# Esquema_PowerBox1.net
KiCad netlist of a schematic drawn in EAGLE
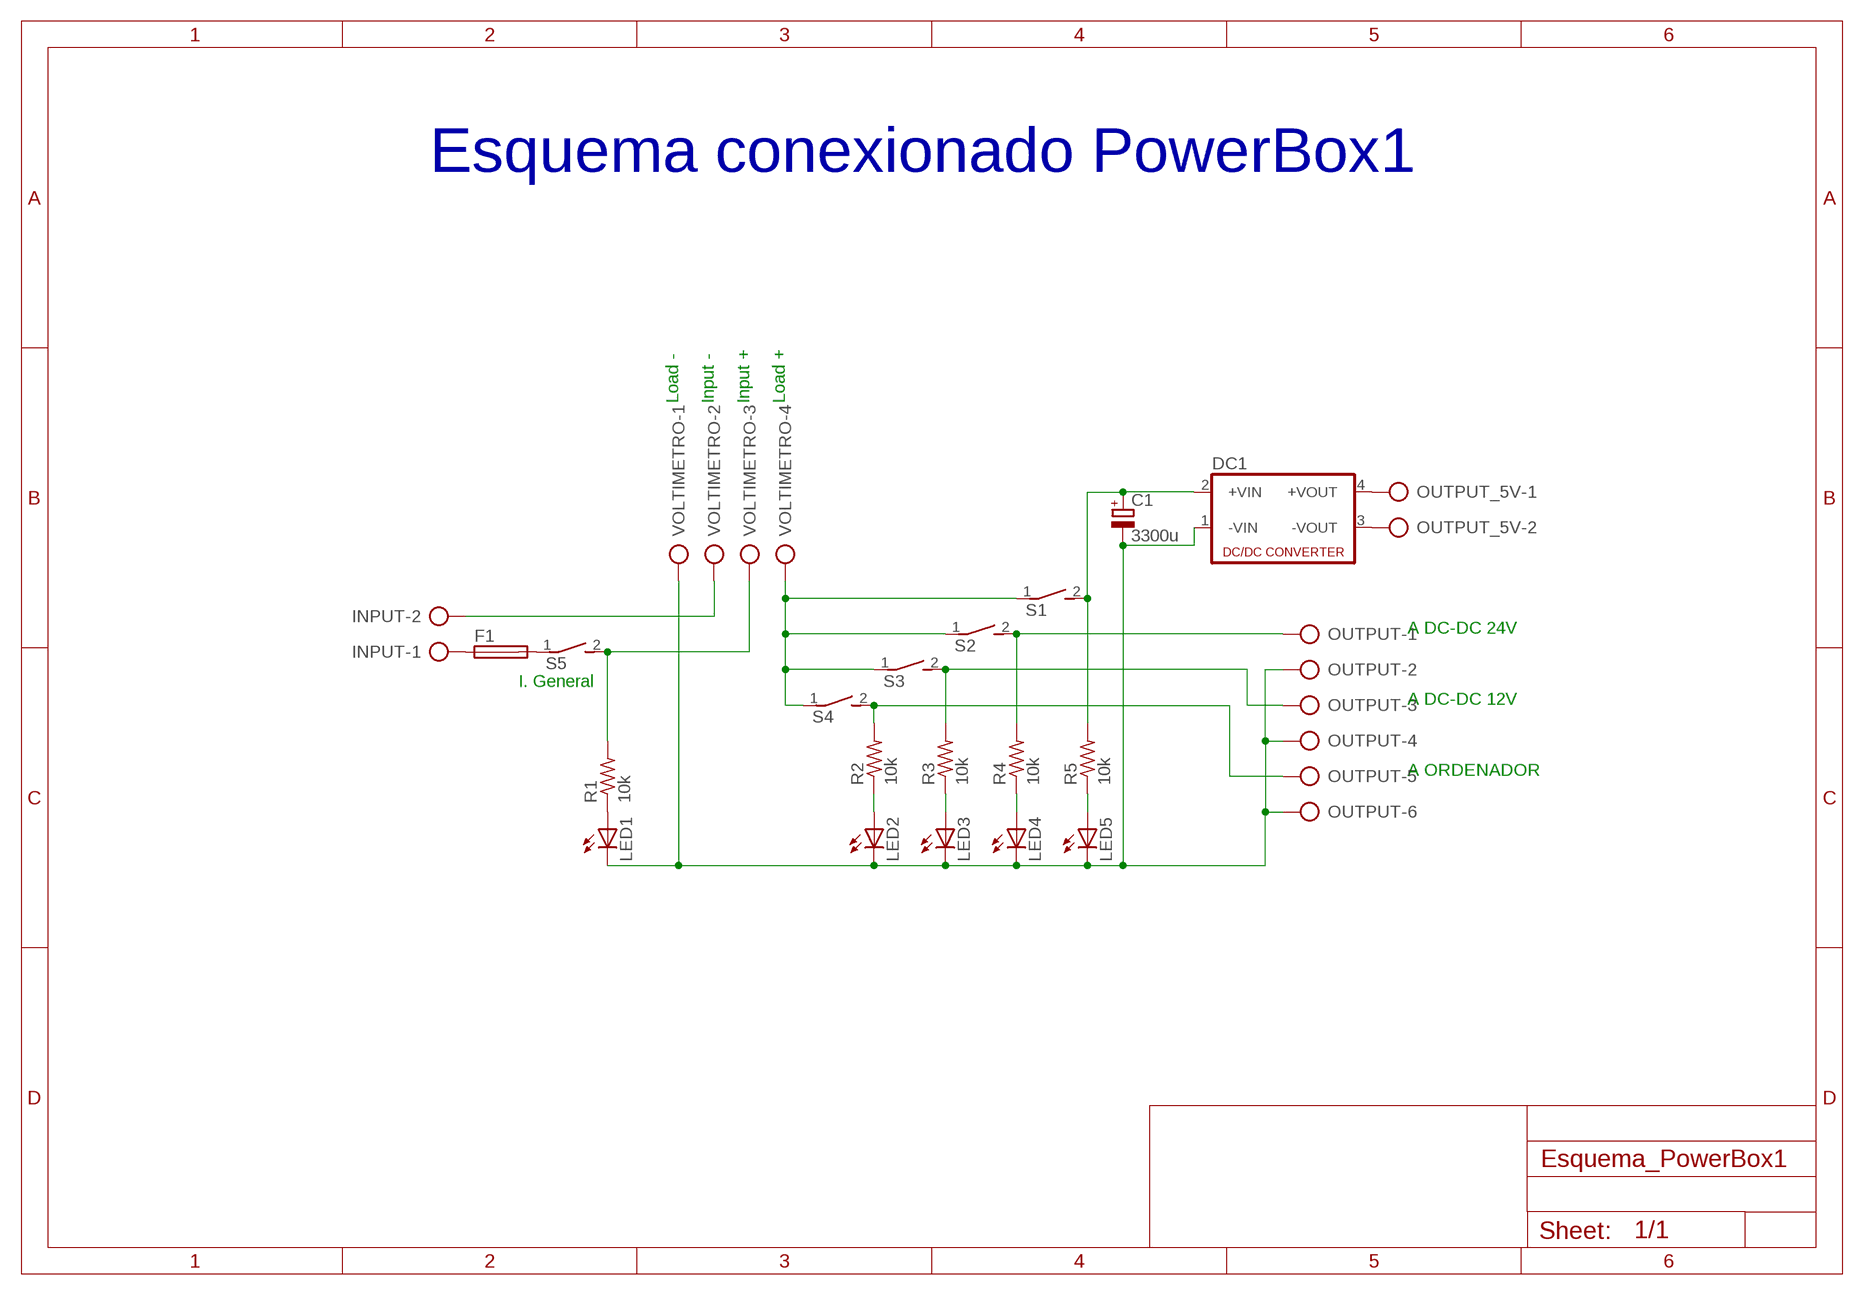
[diagram p0: schematic, sheet 1]

(export (version "E")
  (design (tool "Eeschema 10.0.6"))
  (components
    (comp (ref "C1")
      (value "3300u")
      (footprint "eagle-import:150CLZ-1014")
      (libsource (lib "eagle-import") (part "CPOL-EU150CLZ-1014"))
    )
    (comp (ref "DC1")
      (value "NME")
      (footprint "eagle-import:NME")
      (fields (field (name "MF") "C & D TECHNOLOGIES, INC") (field (name "MPN") "NME1205D"))
      (libsource (lib "eagle-import") (part "NME"))
    )
    (comp (ref "F1")
      (value "PICOFUSE")
      (footprint "eagle-import:PICOFUSE")
      (libsource (lib "eagle-import") (part "PICOFUSE"))
    )
    (comp (ref "INPUT")
      (value "AK500/2")
      (footprint "eagle-import:AK500_2")
      (libsource (lib "eagle-import") (part "AK500/2"))
    )
    (comp (ref "LED1")
      (value "LEDB155")
      (footprint "eagle-import:Q62902-B155")
      (libsource (lib "eagle-import") (part "LEDB155"))
    )
    (comp (ref "LED2")
      (value "LEDB155")
      (footprint "eagle-import:Q62902-B155")
      (libsource (lib "eagle-import") (part "LEDB155"))
    )
    (comp (ref "LED3")
      (value "LEDB155")
      (footprint "eagle-import:Q62902-B155")
      (libsource (lib "eagle-import") (part "LEDB155"))
    )
    (comp (ref "LED4")
      (value "LEDB155")
      (footprint "eagle-import:Q62902-B155")
      (libsource (lib "eagle-import") (part "LEDB155"))
    )
    (comp (ref "LED5")
      (value "LEDB155")
      (footprint "eagle-import:Q62902-B155")
      (libsource (lib "eagle-import") (part "LEDB155"))
    )
    (comp (ref "OUTPUT")
      (value "AK500/6")
      (footprint "eagle-import:AK500_6")
      (libsource (lib "eagle-import") (part "AK500/6"))
    )
    (comp (ref "OUTPUT_5V")
      (value "AK500/2")
      (footprint "eagle-import:AK500_2")
      (libsource (lib "eagle-import") (part "AK500/2"))
    )
    (comp (ref "R1")
      (value "10k")
      (footprint "eagle-import:0207_7")
      (libsource (lib "eagle-import") (part "R-US_0207/7"))
    )
    (comp (ref "R2")
      (value "10k")
      (footprint "eagle-import:0207_7")
      (libsource (lib "eagle-import") (part "R-US_0207/7"))
    )
    (comp (ref "R3")
      (value "10k")
      (footprint "eagle-import:0207_7")
      (libsource (lib "eagle-import") (part "R-US_0207/7"))
    )
    (comp (ref "R4")
      (value "10k")
      (footprint "eagle-import:0207_7")
      (libsource (lib "eagle-import") (part "R-US_0207/7"))
    )
    (comp (ref "R5")
      (value "10k")
      (footprint "eagle-import:0207_7")
      (libsource (lib "eagle-import") (part "R-US_0207/7"))
    )
    (comp (ref "S1")
      (value "DS01E")
      (footprint "eagle-import:DS-01")
      (libsource (lib "eagle-import") (part "DS01E"))
    )
    (comp (ref "S2")
      (value "DS01E")
      (footprint "eagle-import:DS-01")
      (libsource (lib "eagle-import") (part "DS01E"))
    )
    (comp (ref "S3")
      (value "DS01E")
      (footprint "eagle-import:DS-01")
      (libsource (lib "eagle-import") (part "DS01E"))
    )
    (comp (ref "S4")
      (value "DS01E")
      (footprint "eagle-import:DS-01")
      (libsource (lib "eagle-import") (part "DS01E"))
    )
    (comp (ref "S5")
      (value "DS01E")
      (footprint "eagle-import:DS-01")
      (libsource (lib "eagle-import") (part "DS01E"))
    )
    (comp (ref "VOLTIMETRO")
      (value "AK500/4")
      (footprint "eagle-import:AK500_4")
      (libsource (lib "eagle-import") (part "AK500/4"))
    )
  )
  (nets
    (net (code "1") (name "Net-(DC1-+VIN)") (class "Default")
      (node (ref "C1") (pin "+") (pinfunction "+_+") (pintype "passive"))
      (node (ref "DC1") (pin "2") (pinfunction "+VIN_2") (pintype "passive"))
      (node (ref "R5") (pin "2") (pinfunction "2_2") (pintype "passive"))
      (node (ref "S1") (pin "2") (pinfunction "2_2") (pintype "passive"))
    )
    (net (code "2") (name "Net-(DC1-+VOUT)") (class "Default")
      (node (ref "DC1") (pin "4") (pinfunction "+VOUT_4") (pintype "passive"))
      (node (ref "OUTPUT_5V") (pin "1") (pinfunction "KL_1") (pintype "passive"))
    )
    (net (code "3") (name "Net-(DC1--VIN)") (class "Default")
      (node (ref "C1") (pin "-") (pinfunction "-_-") (pintype "passive"))
      (node (ref "DC1") (pin "1") (pinfunction "-VIN_1") (pintype "passive"))
      (node (ref "LED1") (pin "K") (pinfunction "C_K") (pintype "passive"))
      (node (ref "LED2") (pin "K") (pinfunction "C_K") (pintype "passive"))
      (node (ref "LED3") (pin "K") (pinfunction "C_K") (pintype "passive"))
      (node (ref "LED4") (pin "K") (pinfunction "C_K") (pintype "passive"))
      (node (ref "LED5") (pin "K") (pinfunction "C_K") (pintype "passive"))
      (node (ref "OUTPUT") (pin "2") (pinfunction "KL_2") (pintype "passive"))
      (node (ref "OUTPUT") (pin "4") (pinfunction "KL_4") (pintype "passive"))
      (node (ref "OUTPUT") (pin "6") (pinfunction "KL_6") (pintype "passive"))
      (node (ref "VOLTIMETRO") (pin "1") (pinfunction "KL_1") (pintype "passive"))
    )
    (net (code "4") (name "Net-(DC1--VOUT)") (class "Default")
      (node (ref "DC1") (pin "3") (pinfunction "-VOUT_3") (pintype "passive"))
      (node (ref "OUTPUT_5V") (pin "2") (pinfunction "KL_2") (pintype "passive"))
    )
    (net (code "5") (name "Net-(F1-Pad2)") (class "Default")
      (node (ref "F1") (pin "2") (pinfunction "2_2") (pintype "passive"))
      (node (ref "S5") (pin "1") (pinfunction "1_1") (pintype "passive"))
    )
    (net (code "6") (name "Net-(INPUTA-KL)") (class "Default")
      (node (ref "F1") (pin "1") (pinfunction "1_1") (pintype "passive"))
      (node (ref "INPUT") (pin "1") (pinfunction "KL_1") (pintype "passive"))
    )
    (net (code "7") (name "Net-(INPUTB-KL)") (class "Default")
      (node (ref "INPUT") (pin "2") (pinfunction "KL_2") (pintype "passive"))
      (node (ref "VOLTIMETRO") (pin "2") (pinfunction "KL_2") (pintype "passive"))
    )
    (net (code "8") (name "Net-(LED1-PadA)") (class "Default")
      (node (ref "LED1") (pin "A") (pinfunction "A_A") (pintype "passive"))
      (node (ref "R1") (pin "1") (pinfunction "1_1") (pintype "passive"))
    )
    (net (code "9") (name "Net-(LED2-PadA)") (class "Default")
      (node (ref "LED2") (pin "A") (pinfunction "A_A") (pintype "passive"))
      (node (ref "R2") (pin "1") (pinfunction "1_1") (pintype "passive"))
    )
    (net (code "10") (name "Net-(LED3-PadA)") (class "Default")
      (node (ref "LED3") (pin "A") (pinfunction "A_A") (pintype "passive"))
      (node (ref "R3") (pin "1") (pinfunction "1_1") (pintype "passive"))
    )
    (net (code "11") (name "Net-(LED4-PadA)") (class "Default")
      (node (ref "LED4") (pin "A") (pinfunction "A_A") (pintype "passive"))
      (node (ref "R4") (pin "1") (pinfunction "1_1") (pintype "passive"))
    )
    (net (code "12") (name "Net-(LED5-PadA)") (class "Default")
      (node (ref "LED5") (pin "A") (pinfunction "A_A") (pintype "passive"))
      (node (ref "R5") (pin "1") (pinfunction "1_1") (pintype "passive"))
    )
    (net (code "13") (name "Net-(OUTPUTA-KL)") (class "Default")
      (node (ref "OUTPUT") (pin "1") (pinfunction "KL_1") (pintype "passive"))
      (node (ref "R4") (pin "2") (pinfunction "2_2") (pintype "passive"))
      (node (ref "S2") (pin "2") (pinfunction "2_2") (pintype "passive"))
    )
    (net (code "14") (name "Net-(OUTPUTC-KL)") (class "Default")
      (node (ref "OUTPUT") (pin "3") (pinfunction "KL_3") (pintype "passive"))
      (node (ref "R3") (pin "2") (pinfunction "2_2") (pintype "passive"))
      (node (ref "S3") (pin "2") (pinfunction "2_2") (pintype "passive"))
    )
    (net (code "15") (name "Net-(OUTPUTE-KL)") (class "Default")
      (node (ref "OUTPUT") (pin "5") (pinfunction "KL_5") (pintype "passive"))
      (node (ref "R2") (pin "2") (pinfunction "2_2") (pintype "passive"))
      (node (ref "S4") (pin "2") (pinfunction "2_2") (pintype "passive"))
    )
    (net (code "16") (name "Net-(VOLTIMETROC-KL)") (class "Default")
      (node (ref "R1") (pin "2") (pinfunction "2_2") (pintype "passive"))
      (node (ref "S5") (pin "2") (pinfunction "2_2") (pintype "passive"))
      (node (ref "VOLTIMETRO") (pin "3") (pinfunction "KL_3") (pintype "passive"))
    )
    (net (code "17") (name "Net-(VOLTIMETROD-KL)") (class "Default")
      (node (ref "S1") (pin "1") (pinfunction "1_1") (pintype "passive"))
      (node (ref "S2") (pin "1") (pinfunction "1_1") (pintype "passive"))
      (node (ref "S3") (pin "1") (pinfunction "1_1") (pintype "passive"))
      (node (ref "S4") (pin "1") (pinfunction "1_1") (pintype "passive"))
      (node (ref "VOLTIMETRO") (pin "4") (pinfunction "KL_4") (pintype "passive"))
    )
  )
)
